# PCB.net
KiCad netlist of a schematic drawn in EAGLE
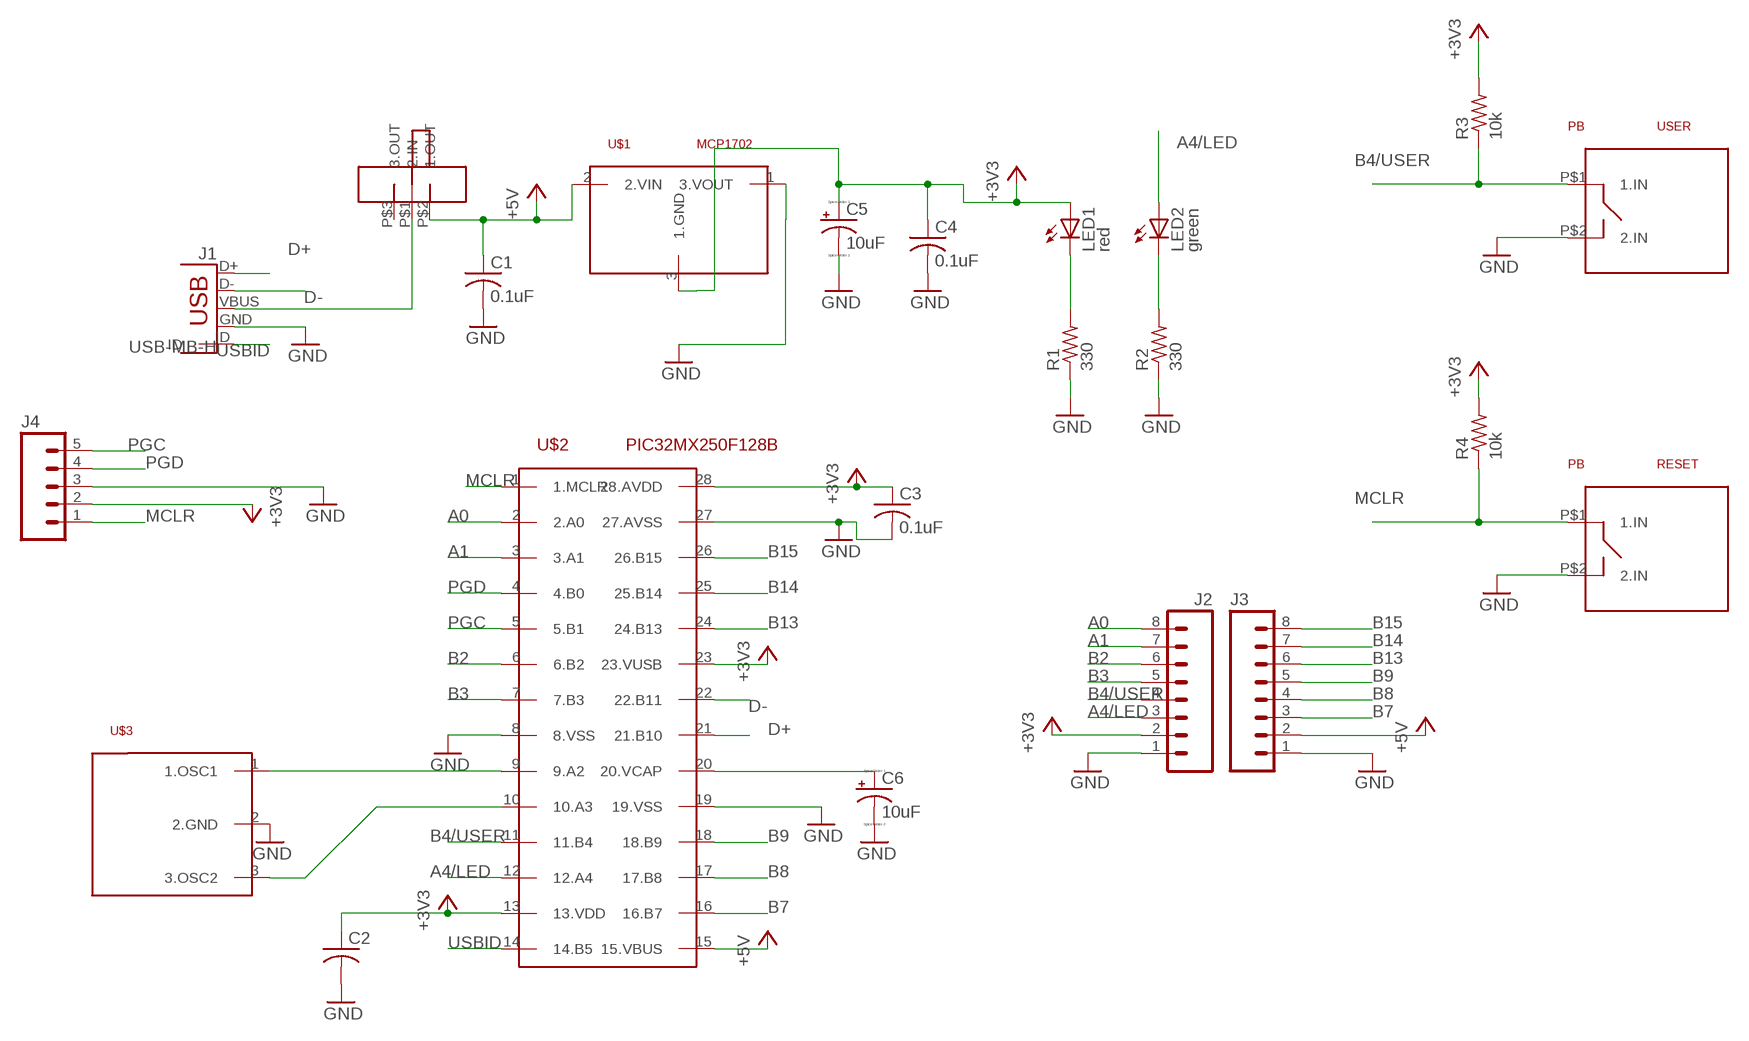
[diagram p0: schematic, sheet 1]

(export (version "E")
  (design (tool "Eeschema 10.0.6"))
  (components
    (comp (ref "C1")
      (value "0.1uF")
      (footprint "eagle-import:C025-025X050")
      (libsource (lib "eagle-import") (part "C-US025-025X050"))
    )
    (comp (ref "C2")
      (value "C-US025-025X050")
      (footprint "eagle-import:C025-025X050")
      (libsource (lib "eagle-import") (part "C-US025-025X050"))
    )
    (comp (ref "C3")
      (value "0.1uF")
      (footprint "eagle-import:C025-025X050")
      (libsource (lib "eagle-import") (part "C-US025-025X050"))
    )
    (comp (ref "C4")
      (value "0.1uF")
      (footprint "eagle-import:C025-025X050")
      (libsource (lib "eagle-import") (part "C-US025-025X050"))
    )
    (comp (ref "C5")
      (value "10uF")
      (footprint "eagle-import:B45181A")
      (libsource (lib "eagle-import") (part "CPOL-USB45181A"))
    )
    (comp (ref "C6")
      (value "10uF")
      (footprint "eagle-import:B45181A")
      (libsource (lib "eagle-import") (part "CPOL-USB45181A"))
    )
    (comp (ref "J1")
      (value "USB-MB-H")
      (footprint "eagle-import:USB-MB-H")
      (libsource (lib "eagle-import") (part "USB-MB-H"))
    )
    (comp (ref "J2")
      (value "M08")
      (footprint "eagle-import:1X08_ROUND")
      (libsource (lib "eagle-import") (part "M08"))
    )
    (comp (ref "J3")
      (value "M08")
      (footprint "eagle-import:1X08_ROUND")
      (libsource (lib "eagle-import") (part "M08"))
    )
    (comp (ref "J4")
      (value "M05PTH")
      (footprint "eagle-import:1X05")
      (libsource (lib "eagle-import") (part "M05PTH"))
    )
    (comp (ref "LED1")
      (value "red")
      (footprint "eagle-import:LED3MM")
      (libsource (lib "eagle-import") (part "LED3MM"))
    )
    (comp (ref "LED2")
      (value "green")
      (footprint "eagle-import:LED3MM")
      (libsource (lib "eagle-import") (part "LED3MM"))
    )
    (comp (ref "R1")
      (value "330")
      (footprint "eagle-import:0207_10")
      (libsource (lib "eagle-import") (part "R-US_0207/10"))
    )
    (comp (ref "R2")
      (value "330")
      (footprint "eagle-import:0207_10")
      (libsource (lib "eagle-import") (part "R-US_0207/10"))
    )
    (comp (ref "R3")
      (value "10k")
      (footprint "eagle-import:0207_10")
      (libsource (lib "eagle-import") (part "R-US_0207/10"))
    )
    (comp (ref "R4")
      (value "10k")
      (footprint "eagle-import:0207_10")
      (libsource (lib "eagle-import") (part "R-US_0207/10"))
    )
    (comp (ref "RESET")
      (value "PB")
      (footprint "eagle-import:PUSHBUTTON")
      (libsource (lib "eagle-import") (part "PB"))
    )
    (comp (ref "U$1")
      (value "MCP1702")
      (footprint "eagle-import:TO92")
      (libsource (lib "eagle-import") (part "MCP1702"))
    )
    (comp (ref "U$2")
      (value "PIC32MX250F128B")
      (footprint "eagle-import:DIL28-3")
      (libsource (lib "eagle-import") (part "PIC32MX250F128B"))
    )
    (comp (ref "U$3")
      (value "CRES")
      (footprint "eagle-import:1X03")
      (libsource (lib "eagle-import") (part "CRES"))
    )
    (comp (ref "U$5")
      (value "SLIDE")
      (footprint "eagle-import:SLIDE")
      (libsource (lib "eagle-import") (part "SLIDE"))
    )
    (comp (ref "USER")
      (value "PB")
      (footprint "eagle-import:PUSHBUTTON")
      (libsource (lib "eagle-import") (part "PB"))
    )
  )
  (nets
    (net (code "1") (name "+3V3") (class "Default")
      (node (ref "C2") (pin "1") (pinfunction "1_1") (pintype "passive"))
      (node (ref "C3") (pin "1") (pinfunction "1_1") (pintype "passive"))
      (node (ref "C4") (pin "1") (pinfunction "1_1") (pintype "passive"))
      (node (ref "C5") (pin "+") (pinfunction "+_+") (pintype "passive"))
      (node (ref "J2") (pin "2") (pinfunction "2_2") (pintype "passive"))
      (node (ref "J4") (pin "2") (pinfunction "2_2") (pintype "passive"))
      (node (ref "LED1") (pin "A") (pinfunction "A_A") (pintype "passive"))
      (node (ref "R3") (pin "2") (pinfunction "2_2") (pintype "passive"))
      (node (ref "R4") (pin "2") (pinfunction "2_2") (pintype "passive"))
      (node (ref "U$1") (pin "3") (pinfunction "1.GND_3") (pintype "bidirectional"))
      (node (ref "U$2") (pin "13") (pinfunction "13.VDD_13") (pintype "bidirectional"))
      (node (ref "U$2") (pin "23") (pinfunction "23.VUSB_23") (pintype "bidirectional"))
      (node (ref "U$2") (pin "28") (pinfunction "28.AVDD_28") (pintype "bidirectional"))
    )
    (net (code "2") (name "+5V") (class "Default")
      (node (ref "C1") (pin "1") (pinfunction "1_1") (pintype "passive"))
      (node (ref "J3") (pin "2") (pinfunction "2_2") (pintype "passive"))
      (node (ref "U$1") (pin "2") (pinfunction "2.VIN_2") (pintype "bidirectional"))
      (node (ref "U$2") (pin "15") (pinfunction "15.VBUS_15") (pintype "bidirectional"))
      (node (ref "U$5") (pin "P$2") (pinfunction "1.OUT_P$2") (pintype "bidirectional"))
    )
    (net (code "3") (name "/A0") (class "Default")
      (node (ref "J2") (pin "8") (pinfunction "8_8") (pintype "passive"))
      (node (ref "U$2") (pin "2") (pinfunction "2.A0_2") (pintype "bidirectional"))
    )
    (net (code "4") (name "/A1") (class "Default")
      (node (ref "J2") (pin "7") (pinfunction "7_7") (pintype "passive"))
      (node (ref "U$2") (pin "3") (pinfunction "3.A1_3") (pintype "bidirectional"))
    )
    (net (code "5") (name "/A4{slash}LED") (class "Default")
      (node (ref "J2") (pin "3") (pinfunction "3_3") (pintype "passive"))
      (node (ref "LED2") (pin "A") (pinfunction "A_A") (pintype "passive"))
      (node (ref "U$2") (pin "12") (pinfunction "12.A4_12") (pintype "bidirectional"))
    )
    (net (code "6") (name "/B2") (class "Default")
      (node (ref "J2") (pin "6") (pinfunction "6_6") (pintype "passive"))
      (node (ref "U$2") (pin "6") (pinfunction "6.B2_6") (pintype "bidirectional"))
    )
    (net (code "7") (name "/B3") (class "Default")
      (node (ref "J2") (pin "5") (pinfunction "5_5") (pintype "passive"))
      (node (ref "U$2") (pin "7") (pinfunction "7.B3_7") (pintype "bidirectional"))
    )
    (net (code "8") (name "/B4{slash}USER") (class "Default")
      (node (ref "J2") (pin "4") (pinfunction "4_4") (pintype "passive"))
      (node (ref "R3") (pin "1") (pinfunction "1_1") (pintype "passive"))
      (node (ref "U$2") (pin "11") (pinfunction "11.B4_11") (pintype "bidirectional"))
      (node (ref "USER") (pin "P$1") (pinfunction "1.IN_P$1") (pintype "bidirectional"))
    )
    (net (code "9") (name "/B7") (class "Default")
      (node (ref "J3") (pin "3") (pinfunction "3_3") (pintype "passive"))
      (node (ref "U$2") (pin "16") (pinfunction "16.B7_16") (pintype "bidirectional"))
    )
    (net (code "10") (name "/B8") (class "Default")
      (node (ref "J3") (pin "4") (pinfunction "4_4") (pintype "passive"))
      (node (ref "U$2") (pin "17") (pinfunction "17.B8_17") (pintype "bidirectional"))
    )
    (net (code "11") (name "/B9") (class "Default")
      (node (ref "J3") (pin "5") (pinfunction "5_5") (pintype "passive"))
      (node (ref "U$2") (pin "18") (pinfunction "18.B9_18") (pintype "bidirectional"))
    )
    (net (code "12") (name "/B13") (class "Default")
      (node (ref "J3") (pin "6") (pinfunction "6_6") (pintype "passive"))
      (node (ref "U$2") (pin "24") (pinfunction "24.B13_24") (pintype "bidirectional"))
    )
    (net (code "13") (name "/B14") (class "Default")
      (node (ref "J3") (pin "7") (pinfunction "7_7") (pintype "passive"))
      (node (ref "U$2") (pin "25") (pinfunction "25.B14_25") (pintype "bidirectional"))
    )
    (net (code "14") (name "/B15") (class "Default")
      (node (ref "J3") (pin "8") (pinfunction "8_8") (pintype "passive"))
      (node (ref "U$2") (pin "26") (pinfunction "26.B15_26") (pintype "bidirectional"))
    )
    (net (code "15") (name "/D+") (class "Default")
      (node (ref "J1") (pin "D+") (pinfunction "D+_D+") (pintype "bidirectional"))
      (node (ref "U$2") (pin "21") (pinfunction "21.B10_21") (pintype "bidirectional"))
    )
    (net (code "16") (name "/D-") (class "Default")
      (node (ref "J1") (pin "D-") (pinfunction "D-_D-") (pintype "bidirectional"))
      (node (ref "U$2") (pin "22") (pinfunction "22.B11_22") (pintype "bidirectional"))
    )
    (net (code "17") (name "/MCLR") (class "Default")
      (node (ref "J4") (pin "1") (pinfunction "1_1") (pintype "passive"))
      (node (ref "R4") (pin "1") (pinfunction "1_1") (pintype "passive"))
      (node (ref "RESET") (pin "P$1") (pinfunction "1.IN_P$1") (pintype "bidirectional"))
      (node (ref "U$2") (pin "1") (pinfunction "1.MCLR_1") (pintype "bidirectional"))
    )
    (net (code "18") (name "/PGC") (class "Default")
      (node (ref "J4") (pin "5") (pinfunction "5_5") (pintype "passive"))
      (node (ref "U$2") (pin "5") (pinfunction "5.B1_5") (pintype "bidirectional"))
    )
    (net (code "19") (name "/PGD") (class "Default")
      (node (ref "J4") (pin "4") (pinfunction "4_4") (pintype "passive"))
      (node (ref "U$2") (pin "4") (pinfunction "4.B0_4") (pintype "bidirectional"))
    )
    (net (code "20") (name "/USBID") (class "Default")
      (node (ref "J1") (pin "ID") (pinfunction "ID_ID") (pintype "bidirectional"))
      (node (ref "U$2") (pin "14") (pinfunction "14.B5_14") (pintype "bidirectional"))
    )
    (net (code "21") (name "GND") (class "Default")
      (node (ref "C1") (pin "2") (pinfunction "2_2") (pintype "passive"))
      (node (ref "C2") (pin "2") (pinfunction "2_2") (pintype "passive"))
      (node (ref "C3") (pin "2") (pinfunction "2_2") (pintype "passive"))
      (node (ref "C4") (pin "2") (pinfunction "2_2") (pintype "passive"))
      (node (ref "C5") (pin "-") (pinfunction "-_-") (pintype "passive"))
      (node (ref "C6") (pin "-") (pinfunction "-_-") (pintype "passive"))
      (node (ref "J1") (pin "GND") (pinfunction "GND_GND") (pintype "bidirectional"))
      (node (ref "J2") (pin "1") (pinfunction "1_1") (pintype "passive"))
      (node (ref "J3") (pin "1") (pinfunction "1_1") (pintype "passive"))
      (node (ref "J4") (pin "3") (pinfunction "3_3") (pintype "passive"))
      (node (ref "R1") (pin "1") (pinfunction "1_1") (pintype "passive"))
      (node (ref "R2") (pin "1") (pinfunction "1_1") (pintype "passive"))
      (node (ref "RESET") (pin "P$2") (pinfunction "2.IN_P$2") (pintype "bidirectional"))
      (node (ref "U$1") (pin "1") (pinfunction "3.VOUT_1") (pintype "bidirectional"))
      (node (ref "U$2") (pin "19") (pinfunction "19.VSS_19") (pintype "bidirectional"))
      (node (ref "U$2") (pin "27") (pinfunction "27.AVSS_27") (pintype "bidirectional"))
      (node (ref "U$2") (pin "8") (pinfunction "8.VSS_8") (pintype "bidirectional"))
      (node (ref "U$3") (pin "2") (pinfunction "2.GND_2") (pintype "bidirectional"))
      (node (ref "USER") (pin "P$2") (pinfunction "2.IN_P$2") (pintype "bidirectional"))
    )
    (net (code "22") (name "Net-(LED1-C)") (class "Default")
      (node (ref "LED1") (pin "K") (pinfunction "C_K") (pintype "passive"))
      (node (ref "R1") (pin "2") (pinfunction "2_2") (pintype "passive"))
    )
    (net (code "23") (name "Net-(LED2-C)") (class "Default")
      (node (ref "LED2") (pin "K") (pinfunction "C_K") (pintype "passive"))
      (node (ref "R2") (pin "2") (pinfunction "2_2") (pintype "passive"))
    )
    (net (code "24") (name "Net-(U$2-9.A2)") (class "Default")
      (node (ref "U$2") (pin "9") (pinfunction "9.A2_9") (pintype "bidirectional"))
      (node (ref "U$3") (pin "1") (pinfunction "1.OSC1_1") (pintype "bidirectional"))
    )
    (net (code "25") (name "Net-(U$2-10.A3)") (class "Default")
      (node (ref "U$2") (pin "10") (pinfunction "10.A3_10") (pintype "bidirectional"))
      (node (ref "U$3") (pin "3") (pinfunction "3.OSC2_3") (pintype "bidirectional"))
    )
    (net (code "26") (name "Net-(U$2-20.VCAP)") (class "Default")
      (node (ref "C6") (pin "+") (pinfunction "+_+") (pintype "passive"))
      (node (ref "U$2") (pin "20") (pinfunction "20.VCAP_20") (pintype "bidirectional"))
    )
    (net (code "27") (name "Net-(U$5-2.IN)") (class "Default")
      (node (ref "J1") (pin "VBUS") (pinfunction "VBUS_VBUS") (pintype "bidirectional"))
      (node (ref "U$5") (pin "P$1") (pinfunction "2.IN_P$1") (pintype "bidirectional"))
    )
    (net (code "28") (name "unconnected-(U$5-3.OUT-PadP$3)") (class "Default")
      (node (ref "U$5") (pin "P$3") (pinfunction "3.OUT_P$3") (pintype "bidirectional"))
    )
  )
)
